# BLUEPILL_full_schematic.net
KiCad netlist of a schematic drawn in EAGLE
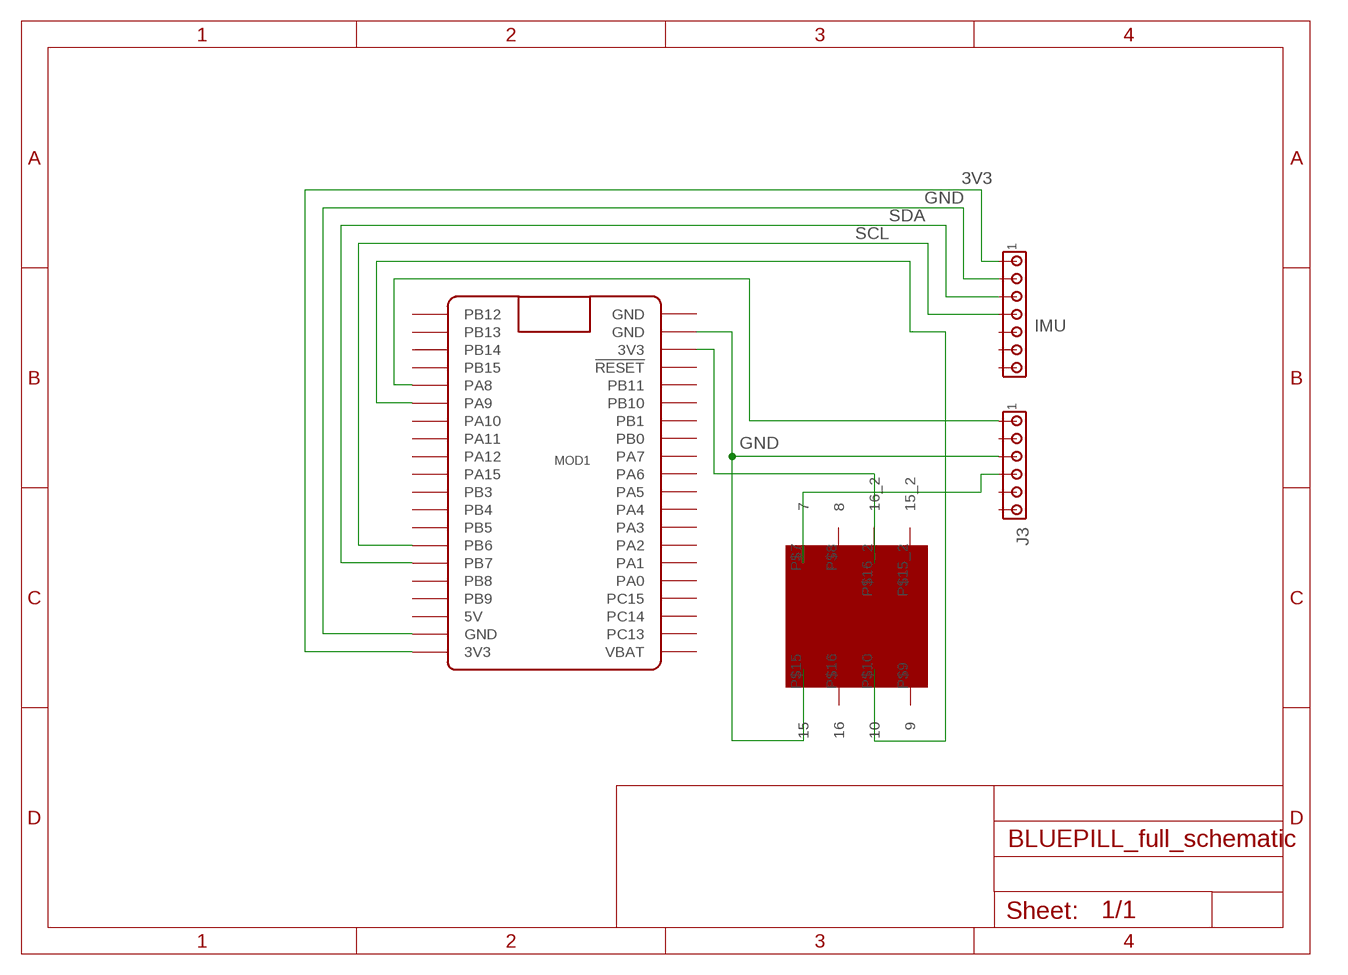
[diagram p0: schematic, sheet 1]

(export (version "E")
  (design (tool "Eeschema 10.0.6"))
  (components
    (comp (ref "IMU")
      (value "MTA07-100")
      (footprint "eagle-import:10X07MTA")
      (libsource (lib "eagle-import") (part "MTA07-100"))
    )
    (comp (ref "J3")
      (value "MTA06-100")
      (footprint "eagle-import:10X06MTA")
      (libsource (lib "eagle-import") (part "MTA06-100"))
    )
    (comp (ref "MOD1")
      (value "BLUE_PILL")
      (footprint "eagle-import:BLUE_PILL")
      (libsource (lib "eagle-import") (part "BLUE_PILL"))
    )
    (comp (ref "U$1")
      (value "MAX3232_CUSTOM")
      (footprint "eagle-import:MAX3232_CUSTOM")
      (libsource (lib "eagle-import") (part "MAX3232_CUSTOM"))
    )
  )
  (nets
    (net (code "1") (name "/3V3") (class "Default")
      (node (ref "IMU") (pin "1") (pinfunction "1_1") (pintype "passive"))
      (node (ref "MOD1") (pin "P$20") (pinfunction "3V3_P$20") (pintype "bidirectional"))
    )
    (net (code "2") (name "/GND") (class "Default")
      (node (ref "IMU") (pin "2") (pinfunction "2_2") (pintype "passive"))
      (node (ref "J3") (pin "3") (pinfunction "3_3") (pintype "passive"))
      (node (ref "MOD1") (pin "P$19") (pinfunction "GND_P$19") (pintype "passive"))
      (node (ref "MOD1") (pin "P$22") (pinfunction "GND_P$22") (pintype "passive"))
      (node (ref "U$1") (pin "P$15") (pinfunction "15_P$15") (pintype "output"))
    )
    (net (code "3") (name "/SCL") (class "Default")
      (node (ref "IMU") (pin "4") (pinfunction "4_4") (pintype "passive"))
      (node (ref "MOD1") (pin "P$14") (pinfunction "PB6_P$14") (pintype "bidirectional"))
    )
    (net (code "4") (name "/SDA") (class "Default")
      (node (ref "IMU") (pin "3") (pinfunction "3_3") (pintype "passive"))
      (node (ref "MOD1") (pin "P$15") (pinfunction "PB7_P$15") (pintype "bidirectional"))
    )
    (net (code "5") (name "Net-(MOD1-PA8)") (class "Default")
      (node (ref "J3") (pin "1") (pinfunction "1_1") (pintype "passive"))
      (node (ref "MOD1") (pin "P$5") (pinfunction "PA8_P$5") (pintype "bidirectional"))
    )
    (net (code "6") (name "Net-(MOD1-PA9)") (class "Default")
      (node (ref "MOD1") (pin "P$6") (pinfunction "PA9_P$6") (pintype "bidirectional"))
      (node (ref "U$1") (pin "P$10") (pinfunction "10_P$10") (pintype "output"))
    )
    (net (code "7") (name "Net-(U$1-7)") (class "Default")
      (node (ref "J3") (pin "4") (pinfunction "4_4") (pintype "passive"))
      (node (ref "U$1") (pin "P$7") (pinfunction "7_P$7") (pintype "output"))
    )
    (net (code "8") (name "Net-(U$1-16_2)") (class "Default")
      (node (ref "MOD1") (pin "P$23") (pinfunction "3V3_P$23") (pintype "bidirectional"))
      (node (ref "U$1") (pin "P$16_2") (pinfunction "16_2_P$16_2") (pintype "output"))
    )
    (net (code "9") (name "unconnected-(IMU-Pad5)") (class "Default")
      (node (ref "IMU") (pin "5") (pinfunction "5_5") (pintype "passive"))
    )
    (net (code "10") (name "unconnected-(IMU-Pad6)") (class "Default")
      (node (ref "IMU") (pin "6") (pinfunction "6_6") (pintype "passive"))
    )
    (net (code "11") (name "unconnected-(IMU-Pad7)") (class "Default")
      (node (ref "IMU") (pin "7") (pinfunction "7_7") (pintype "passive"))
    )
    (net (code "12") (name "unconnected-(J3-Pad2)") (class "Default")
      (node (ref "J3") (pin "2") (pinfunction "2_2") (pintype "passive"))
    )
    (net (code "13") (name "unconnected-(J3-Pad5)") (class "Default")
      (node (ref "J3") (pin "5") (pinfunction "5_5") (pintype "passive"))
    )
    (net (code "14") (name "unconnected-(J3-Pad6)") (class "Default")
      (node (ref "J3") (pin "6") (pinfunction "6_6") (pintype "passive"))
    )
    (net (code "15") (name "unconnected-(MOD1-5V-PadP$18)") (class "Default")
      (node (ref "MOD1") (pin "P$18") (pinfunction "5V_P$18") (pintype "bidirectional"))
    )
    (net (code "16") (name "unconnected-(MOD1-GND-PadP$21)") (class "Default")
      (node (ref "MOD1") (pin "P$21") (pinfunction "GND_P$21") (pintype "passive"))
    )
    (net (code "17") (name "unconnected-(MOD1-PA0-PadP$36)") (class "Default")
      (node (ref "MOD1") (pin "P$36") (pinfunction "PA0_P$36") (pintype "bidirectional"))
    )
    (net (code "18") (name "unconnected-(MOD1-PA1-PadP$35)") (class "Default")
      (node (ref "MOD1") (pin "P$35") (pinfunction "PA1_P$35") (pintype "bidirectional"))
    )
    (net (code "19") (name "unconnected-(MOD1-PA2-PadP$34)") (class "Default")
      (node (ref "MOD1") (pin "P$34") (pinfunction "PA2_P$34") (pintype "bidirectional"))
    )
    (net (code "20") (name "unconnected-(MOD1-PA3-PadP$33)") (class "Default")
      (node (ref "MOD1") (pin "P$33") (pinfunction "PA3_P$33") (pintype "bidirectional"))
    )
    (net (code "21") (name "unconnected-(MOD1-PA4-PadP$32)") (class "Default")
      (node (ref "MOD1") (pin "P$32") (pinfunction "PA4_P$32") (pintype "bidirectional"))
    )
    (net (code "22") (name "unconnected-(MOD1-PA5-PadP$31)") (class "Default")
      (node (ref "MOD1") (pin "P$31") (pinfunction "PA5_P$31") (pintype "bidirectional"))
    )
    (net (code "23") (name "unconnected-(MOD1-PA6-PadP$30)") (class "Default")
      (node (ref "MOD1") (pin "P$30") (pinfunction "PA6_P$30") (pintype "bidirectional"))
    )
    (net (code "24") (name "unconnected-(MOD1-PA7-PadP$29)") (class "Default")
      (node (ref "MOD1") (pin "P$29") (pinfunction "PA7_P$29") (pintype "bidirectional"))
    )
    (net (code "25") (name "unconnected-(MOD1-PA10-PadP$7)") (class "Default")
      (node (ref "MOD1") (pin "P$7") (pinfunction "PA10_P$7") (pintype "bidirectional"))
    )
    (net (code "26") (name "unconnected-(MOD1-PA11-PadP$8)") (class "Default")
      (node (ref "MOD1") (pin "P$8") (pinfunction "PA11_P$8") (pintype "bidirectional"))
    )
    (net (code "27") (name "unconnected-(MOD1-PA12-PadP$9)") (class "Default")
      (node (ref "MOD1") (pin "P$9") (pinfunction "PA12_P$9") (pintype "bidirectional"))
    )
    (net (code "28") (name "unconnected-(MOD1-PA15-PadP$10)") (class "Default")
      (node (ref "MOD1") (pin "P$10") (pinfunction "PA15_P$10") (pintype "bidirectional"))
    )
    (net (code "29") (name "unconnected-(MOD1-PB0-PadP$28)") (class "Default")
      (node (ref "MOD1") (pin "P$28") (pinfunction "PB0_P$28") (pintype "bidirectional"))
    )
    (net (code "30") (name "unconnected-(MOD1-PB1-PadP$27)") (class "Default")
      (node (ref "MOD1") (pin "P$27") (pinfunction "PB1_P$27") (pintype "bidirectional"))
    )
    (net (code "31") (name "unconnected-(MOD1-PB3-PadP$11)") (class "Default")
      (node (ref "MOD1") (pin "P$11") (pinfunction "PB3_P$11") (pintype "bidirectional"))
    )
    (net (code "32") (name "unconnected-(MOD1-PB4-PadP$12)") (class "Default")
      (node (ref "MOD1") (pin "P$12") (pinfunction "PB4_P$12") (pintype "bidirectional"))
    )
    (net (code "33") (name "unconnected-(MOD1-PB5-PadP$13)") (class "Default")
      (node (ref "MOD1") (pin "P$13") (pinfunction "PB5_P$13") (pintype "bidirectional"))
    )
    (net (code "34") (name "unconnected-(MOD1-PB8-PadP$16)") (class "Default")
      (node (ref "MOD1") (pin "P$16") (pinfunction "PB8_P$16") (pintype "bidirectional"))
    )
    (net (code "35") (name "unconnected-(MOD1-PB9-PadP$17)") (class "Default")
      (node (ref "MOD1") (pin "P$17") (pinfunction "PB9_P$17") (pintype "bidirectional"))
    )
    (net (code "36") (name "unconnected-(MOD1-PB10-PadP$26)") (class "Default")
      (node (ref "MOD1") (pin "P$26") (pinfunction "PB10_P$26") (pintype "bidirectional"))
    )
    (net (code "37") (name "unconnected-(MOD1-PB11-PadP$25)") (class "Default")
      (node (ref "MOD1") (pin "P$25") (pinfunction "PB11_P$25") (pintype "bidirectional"))
    )
    (net (code "38") (name "unconnected-(MOD1-PB12-PadP$1)") (class "Default")
      (node (ref "MOD1") (pin "P$1") (pinfunction "PB12_P$1") (pintype "bidirectional"))
    )
    (net (code "39") (name "unconnected-(MOD1-PB13-PadP$2)") (class "Default")
      (node (ref "MOD1") (pin "P$2") (pinfunction "PB13_P$2") (pintype "bidirectional"))
    )
    (net (code "40") (name "unconnected-(MOD1-PB14-PadP$3)") (class "Default")
      (node (ref "MOD1") (pin "P$3") (pinfunction "PB14_P$3") (pintype "bidirectional"))
    )
    (net (code "41") (name "unconnected-(MOD1-PB15-PadP$4)") (class "Default")
      (node (ref "MOD1") (pin "P$4") (pinfunction "PB15_P$4") (pintype "bidirectional"))
    )
    (net (code "42") (name "unconnected-(MOD1-PC13-PadP$39)") (class "Default")
      (node (ref "MOD1") (pin "P$39") (pinfunction "PC13_P$39") (pintype "bidirectional"))
    )
    (net (code "43") (name "unconnected-(MOD1-PC14-PadP$38)") (class "Default")
      (node (ref "MOD1") (pin "P$38") (pinfunction "PC14_P$38") (pintype "bidirectional"))
    )
    (net (code "44") (name "unconnected-(MOD1-PC15-PadP$37)") (class "Default")
      (node (ref "MOD1") (pin "P$37") (pinfunction "PC15_P$37") (pintype "bidirectional"))
    )
    (net (code "45") (name "unconnected-(MOD1-VBAT-PadP$40)") (class "Default")
      (node (ref "MOD1") (pin "P$40") (pinfunction "VBAT_P$40") (pintype "bidirectional"))
    )
    (net (code "46") (name "unconnected-(MOD1-~{RESET}-PadP$24)") (class "Default")
      (node (ref "MOD1") (pin "P$24") (pinfunction "~{RESET}_P$24") (pintype "bidirectional"))
    )
    (net (code "47") (name "unconnected-(U$1-8-PadP$8)") (class "Default")
      (node (ref "U$1") (pin "P$8") (pinfunction "8_P$8") (pintype "output"))
    )
    (net (code "48") (name "unconnected-(U$1-9-PadP$9)") (class "Default")
      (node (ref "U$1") (pin "P$9") (pinfunction "9_P$9") (pintype "output"))
    )
    (net (code "49") (name "unconnected-(U$1-15_2-PadP$15_2)") (class "Default")
      (node (ref "U$1") (pin "P$15_2") (pinfunction "15_2_P$15_2") (pintype "output"))
    )
    (net (code "50") (name "unconnected-(U$1-16-PadP$16)") (class "Default")
      (node (ref "U$1") (pin "P$16") (pinfunction "16_P$16") (pintype "output"))
    )
  )
)
